# Arc_Reactor.net
KiCad netlist of a schematic drawn in EAGLE
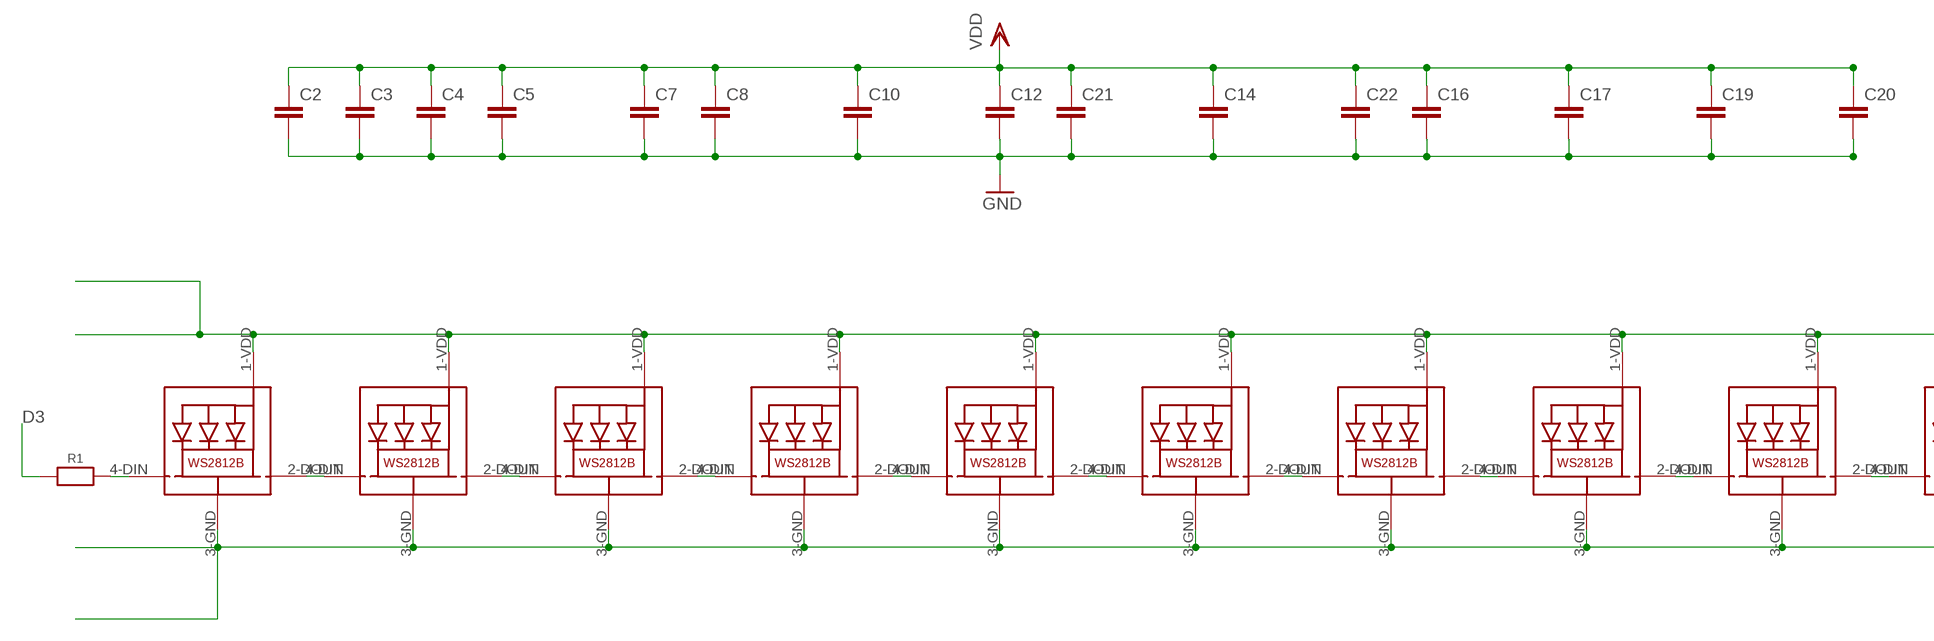
[diagram p0: schematic, sheet 1, part 1 of 2]
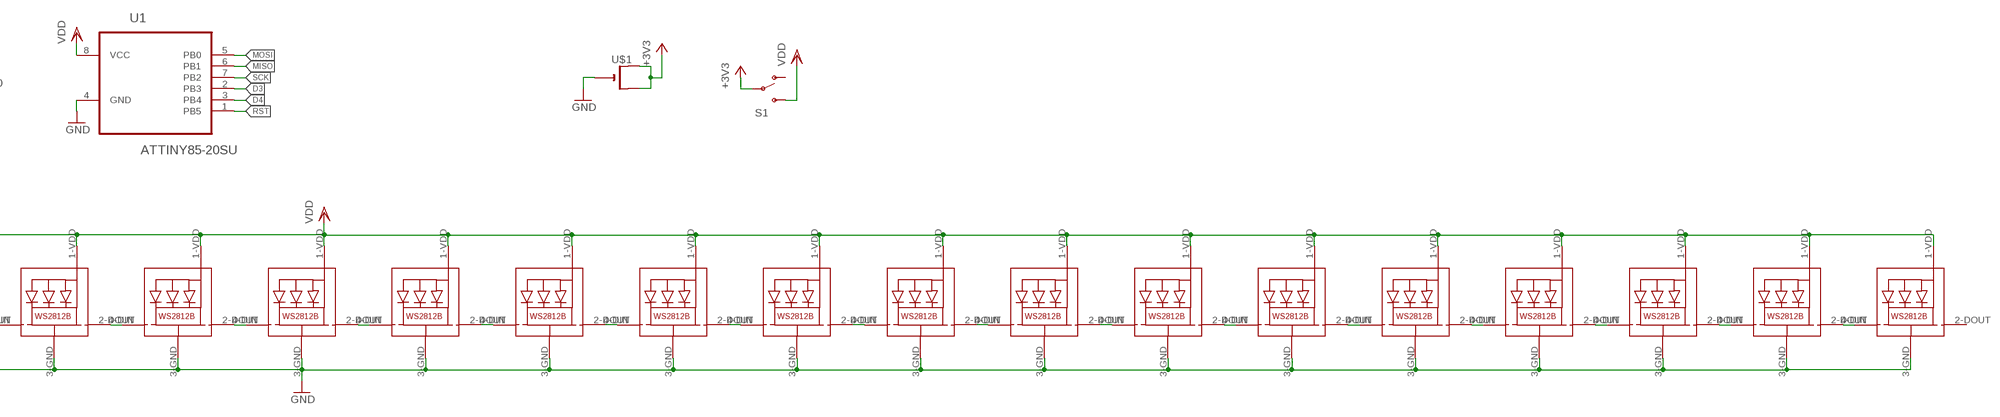
[diagram p1: schematic, sheet 1, part 2 of 2]

(export (version "E")
  (design (tool "Eeschema 10.0.6"))
  (components
    (comp (ref "C2")
      (value "C-EUC0603")
      (footprint "eagle-import:C0603")
      (libsource (lib "eagle-import") (part "C-EUC0603"))
    )
    (comp (ref "C3")
      (value "C-EUC0603")
      (footprint "eagle-import:C0603")
      (libsource (lib "eagle-import") (part "C-EUC0603"))
    )
    (comp (ref "C4")
      (value "C-EUC0603")
      (footprint "eagle-import:C0603")
      (libsource (lib "eagle-import") (part "C-EUC0603"))
    )
    (comp (ref "C5")
      (value "C-EUC0603")
      (footprint "eagle-import:C0603")
      (libsource (lib "eagle-import") (part "C-EUC0603"))
    )
    (comp (ref "C7")
      (value "C-EUC0603")
      (footprint "eagle-import:C0603")
      (libsource (lib "eagle-import") (part "C-EUC0603"))
    )
    (comp (ref "C8")
      (value "C-EUC0603")
      (footprint "eagle-import:C0603")
      (libsource (lib "eagle-import") (part "C-EUC0603"))
    )
    (comp (ref "C10")
      (value "C-EUC0603")
      (footprint "eagle-import:C0603")
      (libsource (lib "eagle-import") (part "C-EUC0603"))
    )
    (comp (ref "C12")
      (value "C-EUC0603")
      (footprint "eagle-import:C0603")
      (libsource (lib "eagle-import") (part "C-EUC0603"))
    )
    (comp (ref "C14")
      (value "C-EUC0603")
      (footprint "eagle-import:C0603")
      (libsource (lib "eagle-import") (part "C-EUC0603"))
    )
    (comp (ref "C16")
      (value "C-EUC0603")
      (footprint "eagle-import:C0603")
      (libsource (lib "eagle-import") (part "C-EUC0603"))
    )
    (comp (ref "C17")
      (value "C-EUC0603")
      (footprint "eagle-import:C0603")
      (libsource (lib "eagle-import") (part "C-EUC0603"))
    )
    (comp (ref "C19")
      (value "C-EUC0603")
      (footprint "eagle-import:C0603")
      (libsource (lib "eagle-import") (part "C-EUC0603"))
    )
    (comp (ref "C20")
      (value "C-EUC0603")
      (footprint "eagle-import:C0603")
      (libsource (lib "eagle-import") (part "C-EUC0603"))
    )
    (comp (ref "C21")
      (value "C-EUC0603")
      (footprint "eagle-import:C0603")
      (libsource (lib "eagle-import") (part "C-EUC0603"))
    )
    (comp (ref "C22")
      (value "C-EUC0603")
      (footprint "eagle-import:C0603")
      (libsource (lib "eagle-import") (part "C-EUC0603"))
    )
    (comp (ref "LED1")
      (value "WS2812B5050")
      (footprint "eagle-import:WS2812B")
      (libsource (lib "eagle-import") (part "WS2812B5050"))
    )
    (comp (ref "LED3")
      (value "WS2812B5050")
      (footprint "eagle-import:WS2812B")
      (libsource (lib "eagle-import") (part "WS2812B5050"))
    )
    (comp (ref "LED4")
      (value "WS2812B5050")
      (footprint "eagle-import:WS2812B")
      (libsource (lib "eagle-import") (part "WS2812B5050"))
    )
    (comp (ref "LED5")
      (value "WS2812B5050")
      (footprint "eagle-import:WS2812B")
      (libsource (lib "eagle-import") (part "WS2812B5050"))
    )
    (comp (ref "LED6")
      (value "WS2812B5050")
      (footprint "eagle-import:WS2812B")
      (libsource (lib "eagle-import") (part "WS2812B5050"))
    )
    (comp (ref "LED7")
      (value "WS2812B5050")
      (footprint "eagle-import:WS2812B")
      (libsource (lib "eagle-import") (part "WS2812B5050"))
    )
    (comp (ref "LED8")
      (value "WS2812B5050")
      (footprint "eagle-import:WS2812B")
      (libsource (lib "eagle-import") (part "WS2812B5050"))
    )
    (comp (ref "LED9")
      (value "WS2812B5050")
      (footprint "eagle-import:WS2812B")
      (libsource (lib "eagle-import") (part "WS2812B5050"))
    )
    (comp (ref "LED10")
      (value "WS2812B5050")
      (footprint "eagle-import:WS2812B")
      (libsource (lib "eagle-import") (part "WS2812B5050"))
    )
    (comp (ref "LED11")
      (value "WS2812B5050")
      (footprint "eagle-import:WS2812B")
      (libsource (lib "eagle-import") (part "WS2812B5050"))
    )
    (comp (ref "LED12")
      (value "WS2812B5050")
      (footprint "eagle-import:WS2812B")
      (libsource (lib "eagle-import") (part "WS2812B5050"))
    )
    (comp (ref "LED13")
      (value "WS2812B5050")
      (footprint "eagle-import:WS2812B")
      (libsource (lib "eagle-import") (part "WS2812B5050"))
    )
    (comp (ref "LED14")
      (value "WS2812B5050")
      (footprint "eagle-import:WS2812B")
      (libsource (lib "eagle-import") (part "WS2812B5050"))
    )
    (comp (ref "LED15")
      (value "WS2812B5050")
      (footprint "eagle-import:WS2812B")
      (libsource (lib "eagle-import") (part "WS2812B5050"))
    )
    (comp (ref "LED16")
      (value "WS2812B5050")
      (footprint "eagle-import:WS2812B")
      (libsource (lib "eagle-import") (part "WS2812B5050"))
    )
    (comp (ref "LED17")
      (value "WS2812B5050")
      (footprint "eagle-import:WS2812B")
      (libsource (lib "eagle-import") (part "WS2812B5050"))
    )
    (comp (ref "LED18")
      (value "WS2812B5050")
      (footprint "eagle-import:WS2812B")
      (libsource (lib "eagle-import") (part "WS2812B5050"))
    )
    (comp (ref "LED19")
      (value "WS2812B5050")
      (footprint "eagle-import:WS2812B")
      (libsource (lib "eagle-import") (part "WS2812B5050"))
    )
    (comp (ref "LED20")
      (value "WS2812B5050")
      (footprint "eagle-import:WS2812B")
      (libsource (lib "eagle-import") (part "WS2812B5050"))
    )
    (comp (ref "LED21")
      (value "WS2812B5050")
      (footprint "eagle-import:WS2812B")
      (libsource (lib "eagle-import") (part "WS2812B5050"))
    )
    (comp (ref "LED22")
      (value "WS2812B5050")
      (footprint "eagle-import:WS2812B")
      (libsource (lib "eagle-import") (part "WS2812B5050"))
    )
    (comp (ref "LED23")
      (value "WS2812B5050")
      (footprint "eagle-import:WS2812B")
      (libsource (lib "eagle-import") (part "WS2812B5050"))
    )
    (comp (ref "LED24")
      (value "WS2812B5050")
      (footprint "eagle-import:WS2812B")
      (libsource (lib "eagle-import") (part "WS2812B5050"))
    )
    (comp (ref "LED25")
      (value "WS2812B5050")
      (footprint "eagle-import:WS2812B")
      (libsource (lib "eagle-import") (part "WS2812B5050"))
    )
    (comp (ref "LED26")
      (value "WS2812B5050")
      (footprint "eagle-import:WS2812B")
      (libsource (lib "eagle-import") (part "WS2812B5050"))
    )
    (comp (ref "R1")
      (value "RESISTOR_0603_NOOUT")
      (footprint "eagle-import:0603-NO")
      (libsource (lib "eagle-import") (part "RESISTOR_0603_NOOUT"))
    )
    (comp (ref "S1")
      (value "SWITCH-SPDTSMD2")
      (footprint "eagle-import:SWITCH-SPDT-SMD")
      (libsource (lib "eagle-import") (part "SWITCH-SPDTSMD2"))
    )
    (comp (ref "U$1")
      (value "CR2032SMT")
      (footprint "eagle-import:CR2032-SMD")
      (libsource (lib "eagle-import") (part "CR2032SMT"))
    )
    (comp (ref "U1")
      (value "ATTINY85-20SU")
      (footprint "eagle-import:SOIC127P798X216-8N")
      (libsource (lib "eagle-import") (part "ATTINY85-20SU"))
    )
  )
  (nets
    (net (code "1") (name "+3V3") (class "Default")
      (node (ref "S1") (pin "2") (pinfunction "P_2") (pintype "passive"))
      (node (ref "U$1") (pin "+$1") (pinfunction "+_+$1") (pintype "passive"))
      (node (ref "U$1") (pin "+$2") (pinfunction "+1_+$2") (pintype "passive"))
    )
    (net (code "2") (name "D3") (class "Default")
      (node (ref "R1") (pin "1") (pinfunction "1_1") (pintype "passive"))
      (node (ref "U1") (pin "2") (pinfunction "PB3_2") (pintype "bidirectional"))
    )
    (net (code "3") (name "D4") (class "Default")
      (node (ref "U1") (pin "3") (pinfunction "PB4_3") (pintype "bidirectional"))
    )
    (net (code "4") (name "GND") (class "Default")
      (node (ref "C10") (pin "2") (pinfunction "2_2") (pintype "passive"))
      (node (ref "C12") (pin "2") (pinfunction "2_2") (pintype "passive"))
      (node (ref "C14") (pin "2") (pinfunction "2_2") (pintype "passive"))
      (node (ref "C16") (pin "2") (pinfunction "2_2") (pintype "passive"))
      (node (ref "C17") (pin "2") (pinfunction "2_2") (pintype "passive"))
      (node (ref "C19") (pin "2") (pinfunction "2_2") (pintype "passive"))
      (node (ref "C2") (pin "2") (pinfunction "2_2") (pintype "passive"))
      (node (ref "C20") (pin "2") (pinfunction "2_2") (pintype "passive"))
      (node (ref "C21") (pin "2") (pinfunction "2_2") (pintype "passive"))
      (node (ref "C22") (pin "2") (pinfunction "2_2") (pintype "passive"))
      (node (ref "C3") (pin "2") (pinfunction "2_2") (pintype "passive"))
      (node (ref "C4") (pin "2") (pinfunction "2_2") (pintype "passive"))
      (node (ref "C5") (pin "2") (pinfunction "2_2") (pintype "passive"))
      (node (ref "C7") (pin "2") (pinfunction "2_2") (pintype "passive"))
      (node (ref "C8") (pin "2") (pinfunction "2_2") (pintype "passive"))
      (node (ref "LED1") (pin "3-GND") (pinfunction "GND_3-GND") (pintype "power_in"))
      (node (ref "LED10") (pin "3-GND") (pinfunction "GND_3-GND") (pintype "power_in"))
      (node (ref "LED11") (pin "3-GND") (pinfunction "GND_3-GND") (pintype "power_in"))
      (node (ref "LED12") (pin "3-GND") (pinfunction "GND_3-GND") (pintype "power_in"))
      (node (ref "LED13") (pin "3-GND") (pinfunction "GND_3-GND") (pintype "power_in"))
      (node (ref "LED14") (pin "3-GND") (pinfunction "GND_3-GND") (pintype "power_in"))
      (node (ref "LED15") (pin "3-GND") (pinfunction "GND_3-GND") (pintype "power_in"))
      (node (ref "LED16") (pin "3-GND") (pinfunction "GND_3-GND") (pintype "power_in"))
      (node (ref "LED17") (pin "3-GND") (pinfunction "GND_3-GND") (pintype "power_in"))
      (node (ref "LED18") (pin "3-GND") (pinfunction "GND_3-GND") (pintype "power_in"))
      (node (ref "LED19") (pin "3-GND") (pinfunction "GND_3-GND") (pintype "power_in"))
      (node (ref "LED20") (pin "3-GND") (pinfunction "GND_3-GND") (pintype "power_in"))
      (node (ref "LED21") (pin "3-GND") (pinfunction "GND_3-GND") (pintype "power_in"))
      (node (ref "LED22") (pin "3-GND") (pinfunction "GND_3-GND") (pintype "power_in"))
      (node (ref "LED23") (pin "3-GND") (pinfunction "GND_3-GND") (pintype "power_in"))
      (node (ref "LED24") (pin "3-GND") (pinfunction "GND_3-GND") (pintype "power_in"))
      (node (ref "LED25") (pin "3-GND") (pinfunction "GND_3-GND") (pintype "power_in"))
      (node (ref "LED26") (pin "3-GND") (pinfunction "GND_3-GND") (pintype "power_in"))
      (node (ref "LED3") (pin "3-GND") (pinfunction "GND_3-GND") (pintype "power_in"))
      (node (ref "LED4") (pin "3-GND") (pinfunction "GND_3-GND") (pintype "power_in"))
      (node (ref "LED5") (pin "3-GND") (pinfunction "GND_3-GND") (pintype "power_in"))
      (node (ref "LED6") (pin "3-GND") (pinfunction "GND_3-GND") (pintype "power_in"))
      (node (ref "LED7") (pin "3-GND") (pinfunction "GND_3-GND") (pintype "power_in"))
      (node (ref "LED8") (pin "3-GND") (pinfunction "GND_3-GND") (pintype "power_in"))
      (node (ref "LED9") (pin "3-GND") (pinfunction "GND_3-GND") (pintype "power_in"))
      (node (ref "U$1") (pin "-") (pinfunction "-_-") (pintype "passive"))
      (node (ref "U1") (pin "4") (pinfunction "GND_4") (pintype "passive"))
    )
    (net (code "5") (name "MISO") (class "Default")
      (node (ref "U1") (pin "6") (pinfunction "PB1_6") (pintype "bidirectional"))
    )
    (net (code "6") (name "MOSI") (class "Default")
      (node (ref "U1") (pin "5") (pinfunction "PB0_5") (pintype "bidirectional"))
    )
    (net (code "7") (name "Net-(LED1-DI)") (class "Default")
      (node (ref "LED1") (pin "4-DIN") (pinfunction "DI_4-DIN") (pintype "input"))
      (node (ref "R1") (pin "2") (pinfunction "2_2") (pintype "passive"))
    )
    (net (code "8") (name "Net-(LED1-DO)") (class "Default")
      (node (ref "LED1") (pin "2-DOUT") (pinfunction "DO_2-DOUT") (pintype "output"))
      (node (ref "LED3") (pin "4-DIN") (pinfunction "DI_4-DIN") (pintype "input"))
    )
    (net (code "9") (name "Net-(LED3-DO)") (class "Default")
      (node (ref "LED3") (pin "2-DOUT") (pinfunction "DO_2-DOUT") (pintype "output"))
      (node (ref "LED4") (pin "4-DIN") (pinfunction "DI_4-DIN") (pintype "input"))
    )
    (net (code "10") (name "Net-(LED4-DO)") (class "Default")
      (node (ref "LED4") (pin "2-DOUT") (pinfunction "DO_2-DOUT") (pintype "output"))
      (node (ref "LED5") (pin "4-DIN") (pinfunction "DI_4-DIN") (pintype "input"))
    )
    (net (code "11") (name "Net-(LED5-DO)") (class "Default")
      (node (ref "LED5") (pin "2-DOUT") (pinfunction "DO_2-DOUT") (pintype "output"))
      (node (ref "LED6") (pin "4-DIN") (pinfunction "DI_4-DIN") (pintype "input"))
    )
    (net (code "12") (name "Net-(LED6-DO)") (class "Default")
      (node (ref "LED6") (pin "2-DOUT") (pinfunction "DO_2-DOUT") (pintype "output"))
      (node (ref "LED7") (pin "4-DIN") (pinfunction "DI_4-DIN") (pintype "input"))
    )
    (net (code "13") (name "Net-(LED7-DO)") (class "Default")
      (node (ref "LED7") (pin "2-DOUT") (pinfunction "DO_2-DOUT") (pintype "output"))
      (node (ref "LED8") (pin "4-DIN") (pinfunction "DI_4-DIN") (pintype "input"))
    )
    (net (code "14") (name "Net-(LED8-DO)") (class "Default")
      (node (ref "LED8") (pin "2-DOUT") (pinfunction "DO_2-DOUT") (pintype "output"))
      (node (ref "LED9") (pin "4-DIN") (pinfunction "DI_4-DIN") (pintype "input"))
    )
    (net (code "15") (name "Net-(LED10-DI)") (class "Default")
      (node (ref "LED10") (pin "4-DIN") (pinfunction "DI_4-DIN") (pintype "input"))
      (node (ref "LED9") (pin "2-DOUT") (pinfunction "DO_2-DOUT") (pintype "output"))
    )
    (net (code "16") (name "Net-(LED10-DO)") (class "Default")
      (node (ref "LED10") (pin "2-DOUT") (pinfunction "DO_2-DOUT") (pintype "output"))
      (node (ref "LED11") (pin "4-DIN") (pinfunction "DI_4-DIN") (pintype "input"))
    )
    (net (code "17") (name "Net-(LED11-DO)") (class "Default")
      (node (ref "LED11") (pin "2-DOUT") (pinfunction "DO_2-DOUT") (pintype "output"))
      (node (ref "LED12") (pin "4-DIN") (pinfunction "DI_4-DIN") (pintype "input"))
    )
    (net (code "18") (name "Net-(LED12-DO)") (class "Default")
      (node (ref "LED12") (pin "2-DOUT") (pinfunction "DO_2-DOUT") (pintype "output"))
      (node (ref "LED13") (pin "4-DIN") (pinfunction "DI_4-DIN") (pintype "input"))
    )
    (net (code "19") (name "Net-(LED13-DO)") (class "Default")
      (node (ref "LED13") (pin "2-DOUT") (pinfunction "DO_2-DOUT") (pintype "output"))
      (node (ref "LED14") (pin "4-DIN") (pinfunction "DI_4-DIN") (pintype "input"))
    )
    (net (code "20") (name "Net-(LED14-DO)") (class "Default")
      (node (ref "LED14") (pin "2-DOUT") (pinfunction "DO_2-DOUT") (pintype "output"))
      (node (ref "LED15") (pin "4-DIN") (pinfunction "DI_4-DIN") (pintype "input"))
    )
    (net (code "21") (name "Net-(LED15-DO)") (class "Default")
      (node (ref "LED15") (pin "2-DOUT") (pinfunction "DO_2-DOUT") (pintype "output"))
      (node (ref "LED16") (pin "4-DIN") (pinfunction "DI_4-DIN") (pintype "input"))
    )
    (net (code "22") (name "Net-(LED16-DO)") (class "Default")
      (node (ref "LED16") (pin "2-DOUT") (pinfunction "DO_2-DOUT") (pintype "output"))
      (node (ref "LED17") (pin "4-DIN") (pinfunction "DI_4-DIN") (pintype "input"))
    )
    (net (code "23") (name "Net-(LED17-DO)") (class "Default")
      (node (ref "LED17") (pin "2-DOUT") (pinfunction "DO_2-DOUT") (pintype "output"))
      (node (ref "LED18") (pin "4-DIN") (pinfunction "DI_4-DIN") (pintype "input"))
    )
    (net (code "24") (name "Net-(LED18-DO)") (class "Default")
      (node (ref "LED18") (pin "2-DOUT") (pinfunction "DO_2-DOUT") (pintype "output"))
      (node (ref "LED19") (pin "4-DIN") (pinfunction "DI_4-DIN") (pintype "input"))
    )
    (net (code "25") (name "Net-(LED19-DO)") (class "Default")
      (node (ref "LED19") (pin "2-DOUT") (pinfunction "DO_2-DOUT") (pintype "output"))
      (node (ref "LED20") (pin "4-DIN") (pinfunction "DI_4-DIN") (pintype "input"))
    )
    (net (code "26") (name "Net-(LED20-DO)") (class "Default")
      (node (ref "LED20") (pin "2-DOUT") (pinfunction "DO_2-DOUT") (pintype "output"))
      (node (ref "LED21") (pin "4-DIN") (pinfunction "DI_4-DIN") (pintype "input"))
    )
    (net (code "27") (name "Net-(LED21-DO)") (class "Default")
      (node (ref "LED21") (pin "2-DOUT") (pinfunction "DO_2-DOUT") (pintype "output"))
      (node (ref "LED22") (pin "4-DIN") (pinfunction "DI_4-DIN") (pintype "input"))
    )
    (net (code "28") (name "Net-(LED22-DO)") (class "Default")
      (node (ref "LED22") (pin "2-DOUT") (pinfunction "DO_2-DOUT") (pintype "output"))
      (node (ref "LED23") (pin "4-DIN") (pinfunction "DI_4-DIN") (pintype "input"))
    )
    (net (code "29") (name "Net-(LED23-DO)") (class "Default")
      (node (ref "LED23") (pin "2-DOUT") (pinfunction "DO_2-DOUT") (pintype "output"))
      (node (ref "LED24") (pin "4-DIN") (pinfunction "DI_4-DIN") (pintype "input"))
    )
    (net (code "30") (name "Net-(LED24-DO)") (class "Default")
      (node (ref "LED24") (pin "2-DOUT") (pinfunction "DO_2-DOUT") (pintype "output"))
      (node (ref "LED25") (pin "4-DIN") (pinfunction "DI_4-DIN") (pintype "input"))
    )
    (net (code "31") (name "Net-(LED25-DO)") (class "Default")
      (node (ref "LED25") (pin "2-DOUT") (pinfunction "DO_2-DOUT") (pintype "output"))
      (node (ref "LED26") (pin "4-DIN") (pinfunction "DI_4-DIN") (pintype "input"))
    )
    (net (code "32") (name "RST") (class "Default")
      (node (ref "U1") (pin "1") (pinfunction "PB5_1") (pintype "bidirectional"))
    )
    (net (code "33") (name "SCK") (class "Default")
      (node (ref "U1") (pin "7") (pinfunction "PB2_7") (pintype "bidirectional"))
    )
    (net (code "34") (name "VDD") (class "Default")
      (node (ref "C10") (pin "1") (pinfunction "1_1") (pintype "passive"))
      (node (ref "C12") (pin "1") (pinfunction "1_1") (pintype "passive"))
      (node (ref "C14") (pin "1") (pinfunction "1_1") (pintype "passive"))
      (node (ref "C16") (pin "1") (pinfunction "1_1") (pintype "passive"))
      (node (ref "C17") (pin "1") (pinfunction "1_1") (pintype "passive"))
      (node (ref "C19") (pin "1") (pinfunction "1_1") (pintype "passive"))
      (node (ref "C2") (pin "1") (pinfunction "1_1") (pintype "passive"))
      (node (ref "C20") (pin "1") (pinfunction "1_1") (pintype "passive"))
      (node (ref "C21") (pin "1") (pinfunction "1_1") (pintype "passive"))
      (node (ref "C22") (pin "1") (pinfunction "1_1") (pintype "passive"))
      (node (ref "C3") (pin "1") (pinfunction "1_1") (pintype "passive"))
      (node (ref "C4") (pin "1") (pinfunction "1_1") (pintype "passive"))
      (node (ref "C5") (pin "1") (pinfunction "1_1") (pintype "passive"))
      (node (ref "C7") (pin "1") (pinfunction "1_1") (pintype "passive"))
      (node (ref "C8") (pin "1") (pinfunction "1_1") (pintype "passive"))
      (node (ref "LED1") (pin "1-VDD") (pinfunction "VDD_1-VDD") (pintype "power_in"))
      (node (ref "LED10") (pin "1-VDD") (pinfunction "VDD_1-VDD") (pintype "power_in"))
      (node (ref "LED11") (pin "1-VDD") (pinfunction "VDD_1-VDD") (pintype "power_in"))
      (node (ref "LED12") (pin "1-VDD") (pinfunction "VDD_1-VDD") (pintype "power_in"))
      (node (ref "LED13") (pin "1-VDD") (pinfunction "VDD_1-VDD") (pintype "power_in"))
      (node (ref "LED14") (pin "1-VDD") (pinfunction "VDD_1-VDD") (pintype "power_in"))
      (node (ref "LED15") (pin "1-VDD") (pinfunction "VDD_1-VDD") (pintype "power_in"))
      (node (ref "LED16") (pin "1-VDD") (pinfunction "VDD_1-VDD") (pintype "power_in"))
      (node (ref "LED17") (pin "1-VDD") (pinfunction "VDD_1-VDD") (pintype "power_in"))
      (node (ref "LED18") (pin "1-VDD") (pinfunction "VDD_1-VDD") (pintype "power_in"))
      (node (ref "LED19") (pin "1-VDD") (pinfunction "VDD_1-VDD") (pintype "power_in"))
      (node (ref "LED20") (pin "1-VDD") (pinfunction "VDD_1-VDD") (pintype "power_in"))
      (node (ref "LED21") (pin "1-VDD") (pinfunction "VDD_1-VDD") (pintype "power_in"))
      (node (ref "LED22") (pin "1-VDD") (pinfunction "VDD_1-VDD") (pintype "power_in"))
      (node (ref "LED23") (pin "1-VDD") (pinfunction "VDD_1-VDD") (pintype "power_in"))
      (node (ref "LED24") (pin "1-VDD") (pinfunction "VDD_1-VDD") (pintype "power_in"))
      (node (ref "LED25") (pin "1-VDD") (pinfunction "VDD_1-VDD") (pintype "power_in"))
      (node (ref "LED26") (pin "1-VDD") (pinfunction "VDD_1-VDD") (pintype "power_in"))
      (node (ref "LED3") (pin "1-VDD") (pinfunction "VDD_1-VDD") (pintype "power_in"))
      (node (ref "LED4") (pin "1-VDD") (pinfunction "VDD_1-VDD") (pintype "power_in"))
      (node (ref "LED5") (pin "1-VDD") (pinfunction "VDD_1-VDD") (pintype "power_in"))
      (node (ref "LED6") (pin "1-VDD") (pinfunction "VDD_1-VDD") (pintype "power_in"))
      (node (ref "LED7") (pin "1-VDD") (pinfunction "VDD_1-VDD") (pintype "power_in"))
      (node (ref "LED8") (pin "1-VDD") (pinfunction "VDD_1-VDD") (pintype "power_in"))
      (node (ref "LED9") (pin "1-VDD") (pinfunction "VDD_1-VDD") (pintype "power_in"))
      (node (ref "S1") (pin "3") (pinfunction "S_3") (pintype "passive"))
      (node (ref "U1") (pin "8") (pinfunction "VCC_8") (pintype "power_in"))
    )
    (net (code "35") (name "unconnected-(LED26-DO-Pad2-DOUT)") (class "Default")
      (node (ref "LED26") (pin "2-DOUT") (pinfunction "DO_2-DOUT") (pintype "output"))
    )
    (net (code "36") (name "unconnected-(S1-O-Pad1)") (class "Default")
      (node (ref "S1") (pin "1") (pinfunction "O_1") (pintype "passive"))
    )
  )
)
